# PWR_Supply.net
KiCad netlist of a schematic drawn in Altium Designer
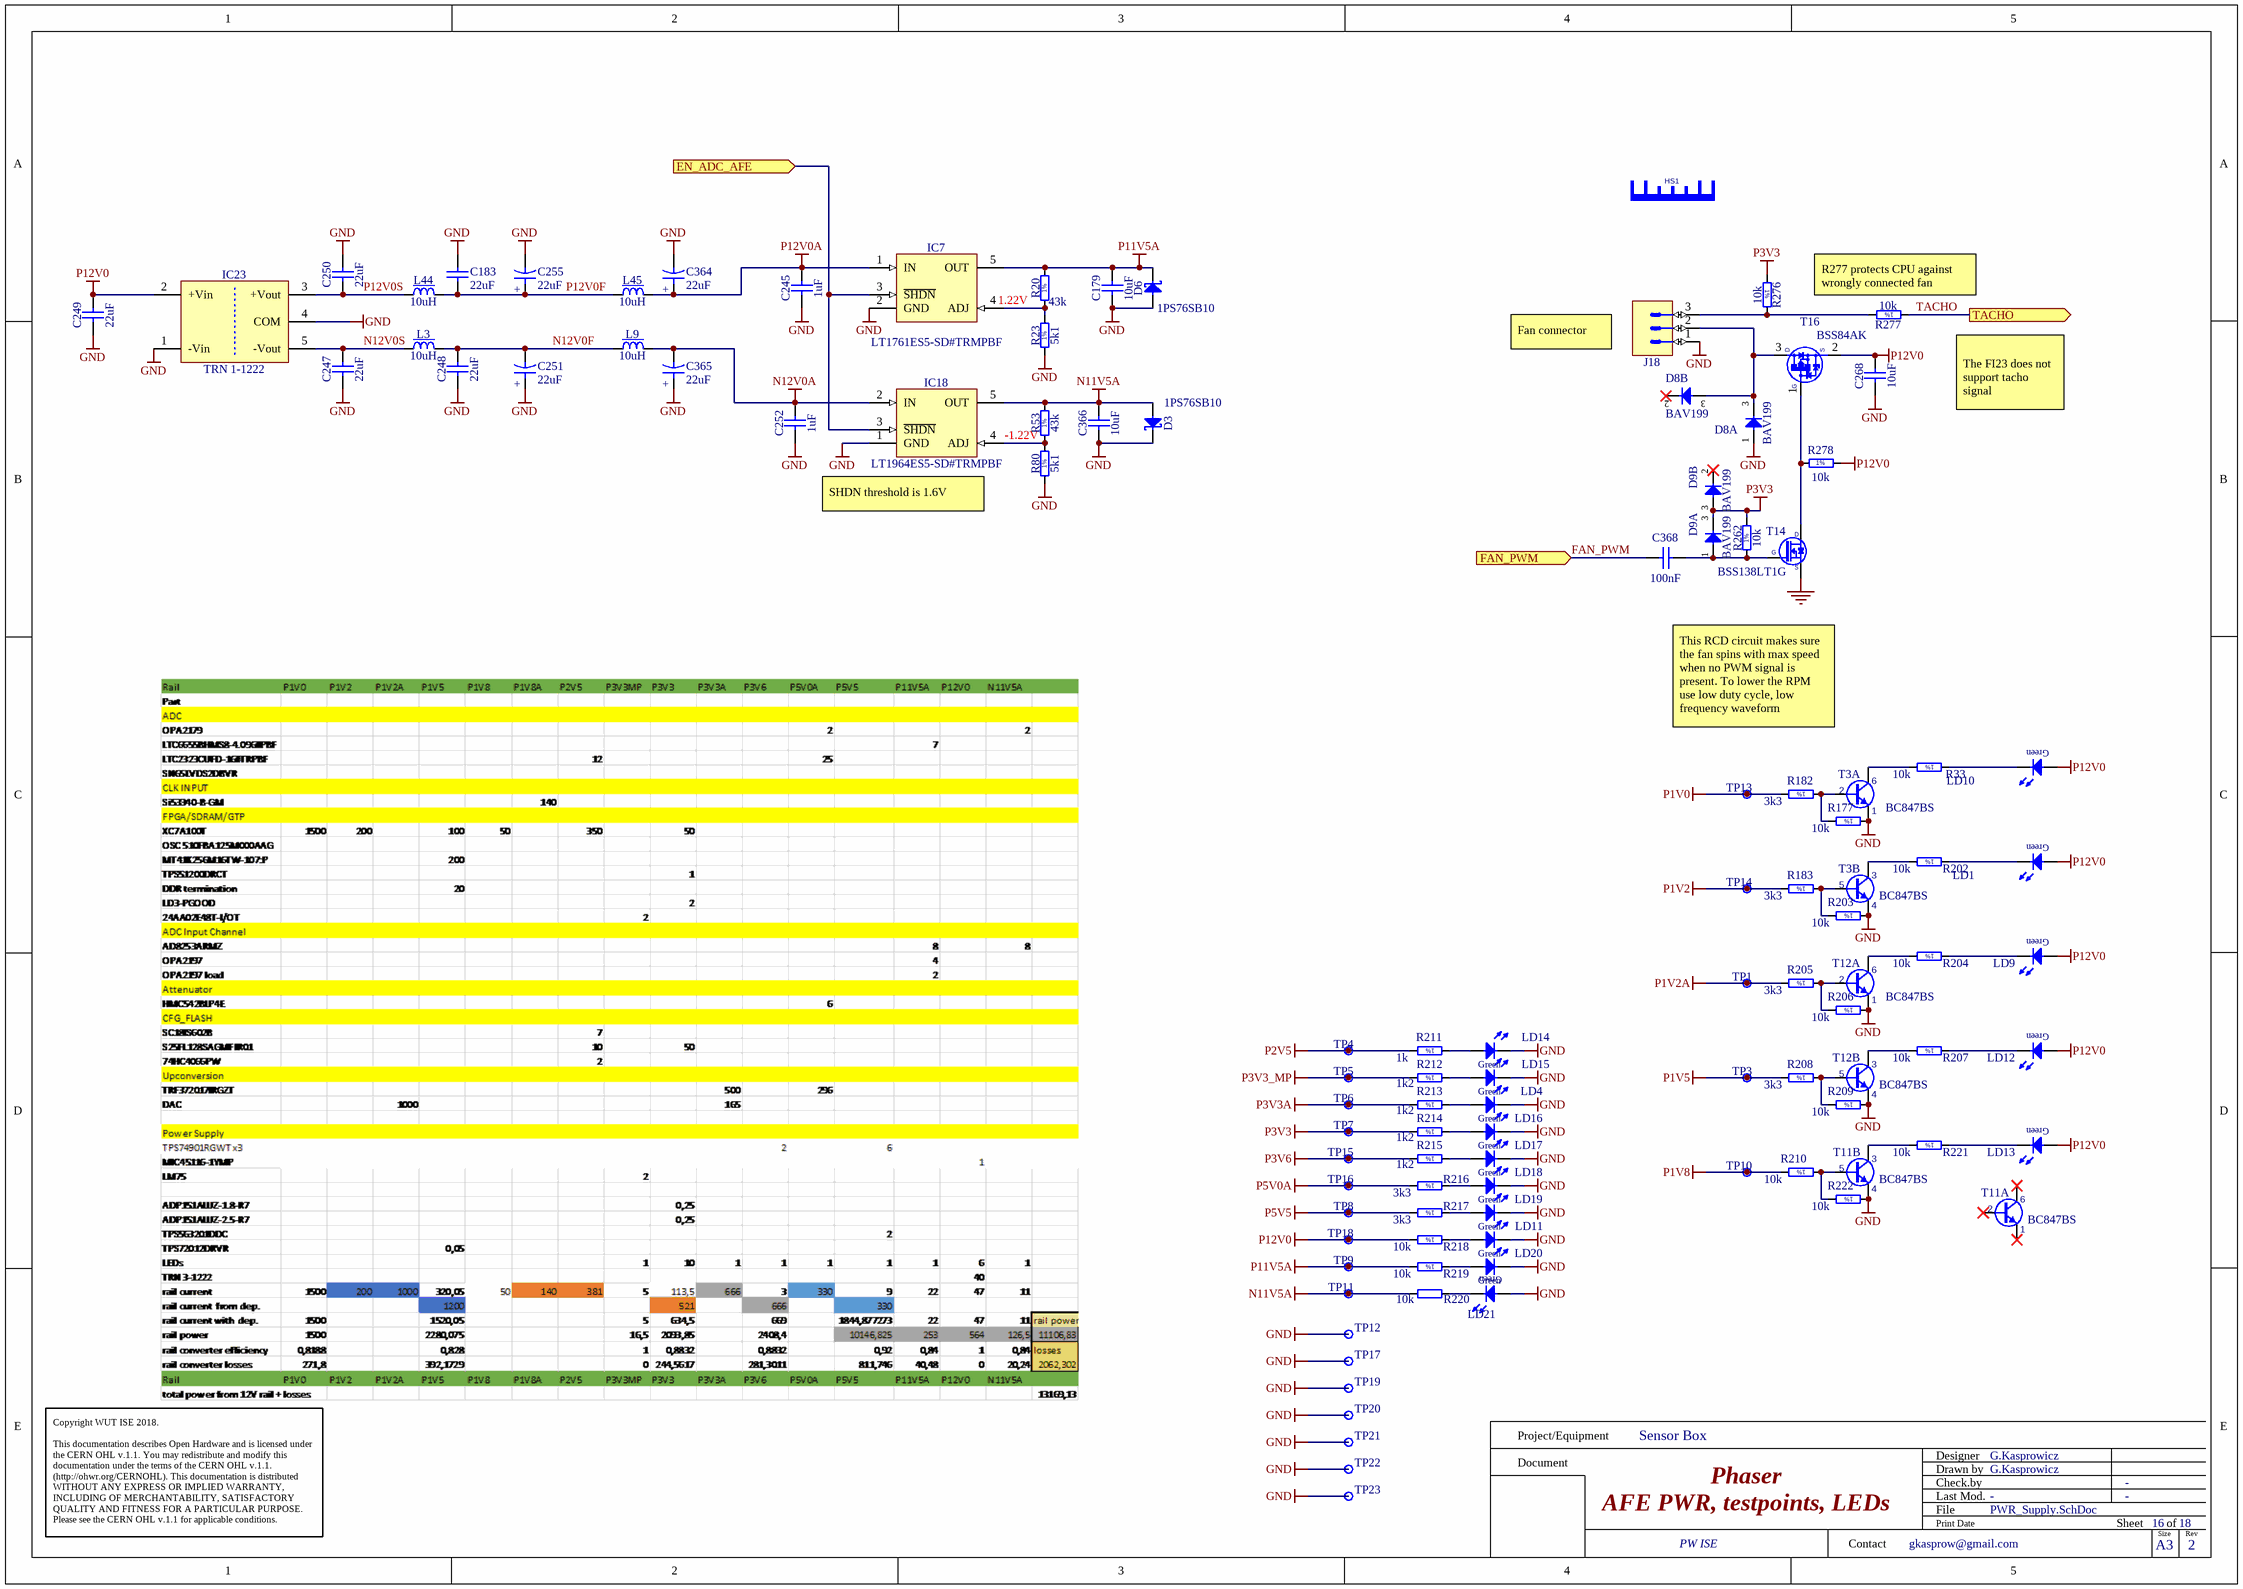
[diagram p0: PWR_Supply.SchDoc]

(export (version "E")
  (design (tool "Eeschema 10.0.6"))
  (components
    (comp (ref "C179")
      (value "10uF")
      (footprint "CAPC2012X135N")
      (description "Non-polarised capacitor")
      (fields
        (field (name "PART NUMBER") "CC0805_10UF_16V_10%_X5R")
        (field (name "VOLTAGE") "16V")
        (field (name "AUTHOR") "CERN DEM JLC")
      )
      (libsource (lib "Capacitors") (part "Capacitor - non polarized"))
    )
    (comp (ref "C183")
      (value "22uF")
      (footprint "CAPC2012X135N")
      (description "Non-polarised capacitor")
      (fields
        (field (name "PART NUMBER") "CC0805_22UF_16V_10%_X5R")
        (field (name "VOLTAGE") "16V")
        (field (name "AUTHOR") "CERN DEM JLC")
      )
      (libsource (lib "Capacitors") (part "Capacitor - non polarized"))
    )
    (comp (ref "C245")
      (value "1uF")
      (footprint "CAPC1608X87N")
      (description "Non-polarised capacitor")
      (fields
        (field (name "PART NUMBER") "CC0603_1UF_25V_10%_X7R")
        (field (name "VOLTAGE") "25V")
        (field (name "AUTHOR") "CERN DEM JLC")
      )
      (libsource (lib "Capacitors") (part "Capacitor - non polarized"))
    )
    (comp (ref "C247")
      (value "22uF")
      (footprint "CAPC2012X135N")
      (description "Non-polarised capacitor")
      (fields
        (field (name "PART NUMBER") "CC0805_22UF_16V_10%_X5R")
        (field (name "VOLTAGE") "16V")
        (field (name "AUTHOR") "CERN DEM JLC")
      )
      (libsource (lib "Capacitors") (part "Capacitor - non polarized"))
    )
    (comp (ref "C248")
      (value "22uF")
      (footprint "CAPC2012X135N")
      (description "Non-polarised capacitor")
      (fields
        (field (name "PART NUMBER") "CC0805_22UF_16V_10%_X5R")
        (field (name "VOLTAGE") "16V")
        (field (name "AUTHOR") "CERN DEM JLC")
      )
      (libsource (lib "Capacitors") (part "Capacitor - non polarized"))
    )
    (comp (ref "C249")
      (value "22uF")
      (footprint "CAPC2012X135N")
      (description "Non-polarised capacitor")
      (fields
        (field (name "PART NUMBER") "CC0805_22UF_16V_10%_X5R")
        (field (name "VOLTAGE") "16V")
        (field (name "AUTHOR") "CERN DEM JLC")
      )
      (libsource (lib "Capacitors") (part "Capacitor - non polarized"))
    )
    (comp (ref "C250")
      (value "22uF")
      (footprint "CAPC2012X135N")
      (description "Non-polarised capacitor")
      (fields
        (field (name "PART NUMBER") "CC0805_22UF_16V_10%_X5R")
        (field (name "VOLTAGE") "16V")
        (field (name "AUTHOR") "CERN DEM JLC")
      )
      (libsource (lib "Capacitors") (part "Capacitor - non polarized"))
    )
    (comp (ref "C251")
      (value "22uF")
      (footprint "CAPMP3528X210N")
      (description "Polarised capacitor")
      (fields
        (field (name "PART NUMBER") "CTE3528-21_22UF_10V_10%_LESR0700")
        (field (name "VOLTAGE") "10V")
        (field (name "AUTHOR") "CERN DEM JLC")
      )
      (libsource (lib "Capacitors") (part "Capacitor - polarized"))
    )
    (comp (ref "C252")
      (value "1uF")
      (footprint "CAPC1608X87N")
      (description "Non-polarised capacitor")
      (fields
        (field (name "PART NUMBER") "CC0603_1UF_25V_10%_X7R")
        (field (name "VOLTAGE") "25V")
        (field (name "AUTHOR") "CERN DEM JLC")
      )
      (libsource (lib "Capacitors") (part "Capacitor - non polarized"))
    )
    (comp (ref "C255")
      (value "22uF")
      (footprint "CAPMP3528X210N")
      (description "Polarised capacitor")
      (fields
        (field (name "PART NUMBER") "CTE3528-21_22UF_10V_10%_LESR0700")
        (field (name "VOLTAGE") "10V")
        (field (name "AUTHOR") "CERN DEM JLC")
      )
      (libsource (lib "Capacitors") (part "Capacitor - polarized"))
    )
    (comp (ref "C268")
      (value "10uF")
      (footprint "CAPC2012X135N")
      (description "Non-polarised capacitor")
      (fields
        (field (name "PART NUMBER") "CC0805_10UF_16V_10%_X5R")
        (field (name "VOLTAGE") "16V")
        (field (name "AUTHOR") "CERN DEM JLC")
      )
      (libsource (lib "Capacitors") (part "Capacitor - non polarized"))
    )
    (comp (ref "C364")
      (value "22uF")
      (footprint "CAPMP3528X210N")
      (description "Polarised capacitor")
      (fields
        (field (name "PART NUMBER") "CTE3528-21_22UF_10V_10%_LESR0700")
        (field (name "VOLTAGE") "10V")
        (field (name "AUTHOR") "CERN DEM JLC")
      )
      (libsource (lib "Capacitors") (part "Capacitor - polarized"))
    )
    (comp (ref "C365")
      (value "22uF")
      (footprint "CAPMP3528X210N")
      (description "Polarised capacitor")
      (fields
        (field (name "PART NUMBER") "CTE3528-21_22UF_10V_10%_LESR0700")
        (field (name "VOLTAGE") "10V")
        (field (name "AUTHOR") "CERN DEM JLC")
      )
      (libsource (lib "Capacitors") (part "Capacitor - polarized"))
    )
    (comp (ref "C366")
      (value "10uF")
      (footprint "CAPC2012X135N")
      (description "Non-polarised capacitor")
      (fields
        (field (name "PART NUMBER") "CC0805_10UF_16V_10%_X5R")
        (field (name "VOLTAGE") "16V")
        (field (name "AUTHOR") "CERN DEM JLC")
      )
      (libsource (lib "Capacitors") (part "Capacitor - non polarized"))
    )
    (comp (ref "C368")
      (value "100nF")
      (footprint "CAPC0603X33N")
      (description "Non-polarised capacitor")
      (fields
        (field (name "PART NUMBER") "CC0201_100NF_6.3V_10%_X5R")
        (field (name "VOLTAGE") "6.3V")
        (field (name "AUTHOR") "CERN DEM JLC")
      )
      (libsource (lib "Capacitors") (part "Capacitor - non polarized"))
    )
    (comp (ref "D3")
      (value "1PS76SB10")
      (footprint "SOD2512X110N")
      (description "Schottky Diode")
      (fields
        (field (name "VOLTAGE") "30V")
        (field (name "POWER") "200mA")
        (field (name "AUTHOR") "CERN DEM JLC")
      )
      (libsource (lib "ICs And Semiconductors") (part "Diode Schottky"))
    )
    (comp (ref "D6")
      (value "1PS76SB10")
      (footprint "SOD2512X110N")
      (description "Schottky Diode")
      (fields
        (field (name "VOLTAGE") "30V")
        (field (name "POWER") "200mA")
        (field (name "AUTHOR") "CERN DEM JLC")
      )
      (libsource (lib "ICs And Semiconductors") (part "Diode Schottky"))
    )
    (comp (ref "D8")
      (value "BAV199")
      (footprint "SOT95P240X110-3N")
      (description "Serial Diode")
      (fields
        (field (name "VOLTAGE") "75V")
        (field (name "POWER") "250mW")
        (field (name "AUTHOR") "CERN DEM JMW")
      )
      (libsource (lib "ICs And Semiconductors") (part "Diode x2 A1C3_A3C2"))
    )
    (comp (ref "D9")
      (value "BAV199")
      (footprint "SOT95P240X110-3N")
      (description "Serial Diode")
      (fields
        (field (name "VOLTAGE") "75V")
        (field (name "POWER") "250mW")
        (field (name "AUTHOR") "CERN DEM JMW")
      )
      (libsource (lib "ICs And Semiconductors") (part "Diode x2 A1C3_A3C2"))
    )
    (comp (ref "HS1")
      (value "RADIAN_FI23")
      (footprint "RADIAN_FI23")
      (description "Heat Sink Without Pad")
      (fields
        (field (name "MANUFACTURER") "Radian Thermal Products, Inc.")
        (field (name "MANUFACTURER PART NUMBER") "FI23+BU+T725")
      )
      (libsource (lib "Schlib1") (part "RADIAN_FI23"))
    )
    (comp (ref "IC7")
      (value "LT1761ES5-SD#TRMPBF")
      (footprint "SOT95P280X100-5N")
      (description "100mA, Low Noise, LDO Micropower Adjustable Regulator in SOT-23")
      (fields (field (name "MANUFACTURER") "LINEAR TECHNOLOGY") (field (name "AUTHOR") "CERN DEM JLC"))
      (libsource (lib "ICs And Semiconductors") (part "LT1761-SD"))
    )
    (comp (ref "IC18")
      (value "LT1964ES5-SD#TRMPBF")
      (footprint "SOT95P280X100-5N")
      (description "200mA, Low Noise, Low Dropout Negative Micropower Regulator")
      (fields (field (name "MANUFACTURER") "LINEAR TECHNOLOGY") (field (name "AUTHOR") "CERN DEM JLC"))
      (libsource (lib "ICs And Semiconductors") (part "LT1964-SD"))
    )
    (comp (ref "IC23")
      (value "TRN 1-1222")
      (footprint "DCDC_TRACO_TRN1")
      (description "9-18VDC to ±12V, Iout (max) ±45mA, 1W DC-DC Converter")
      (fields (field (name "MANUFACTURER") "TRACO POWER") (field (name "AUTHOR") "GK"))
      (libsource (lib "Regulators_SMPS") (part "DCDC_TRACO_TRN 1-1222"))
    )
    (comp (ref "J18")
      (value "KK®")
      (footprint "MOLEX_22-27-2031")
      (description "Connector 3 Male")
      (fields
        (field (name "PART NUMBER") "MOLEX_22-27-2031")
        (field (name "MANUFACTURER") "MOLEX")
        (field (name "AUTHOR") "CERN DEM JLC")
      )
      (libsource (lib "Connectors") (part "Connector 3 Male"))
    )
    (comp (ref "L3")
      (value "10uH")
      (footprint "IND_MURATA-PS_8400")
      (description "Inductor With Core")
      (fields
        (field (name "PART NUMBER") "IND_10UH_10%_MURATA-PS_8400")
        (field (name "POWER") "950mA")
        (field (name "AUTHOR") "CERN DEM JLC")
      )
      (libsource (lib "Inductors & Transformers") (part "Inductor With Magnetic core"))
    )
    (comp (ref "L9")
      (value "10uH")
      (footprint "IND_MURATA-PS_8400")
      (description "Inductor With Core")
      (fields
        (field (name "PART NUMBER") "IND_10UH_10%_MURATA-PS_8400")
        (field (name "POWER") "950mA")
        (field (name "AUTHOR") "CERN DEM JLC")
      )
      (libsource (lib "Inductors & Transformers") (part "Inductor With Magnetic core"))
    )
    (comp (ref "L44")
      (value "10uH")
      (footprint "IND_MURATA-PS_8400")
      (description "Inductor With Core")
      (fields
        (field (name "PART NUMBER") "IND_10UH_10%_MURATA-PS_8400")
        (field (name "POWER") "950mA")
        (field (name "AUTHOR") "CERN DEM JLC")
      )
      (libsource (lib "Inductors & Transformers") (part "Inductor With Magnetic core"))
    )
    (comp (ref "L45")
      (value "10uH")
      (footprint "IND_MURATA-PS_8400")
      (description "Inductor With Core")
      (fields
        (field (name "PART NUMBER") "IND_10UH_10%_MURATA-PS_8400")
        (field (name "POWER") "950mA")
        (field (name "AUTHOR") "CERN DEM JLC")
      )
      (libsource (lib "Inductors & Transformers") (part "Inductor With Magnetic core"))
    )
    (comp (ref "LD1")
      (value "Green")
      (footprint "LED_KINGBRIGHT_KPH-1608CGCKr")
      (description "Green 0603")
      (fields
        (field (name "PART NUMBER") "LED_KINGBRIGHT_KPH-1608CGCK")
        (field (name "MANUFACTURER") "KINGBRIGHT")
        (field (name "AUTHOR") "CERN DEM JLC")
      )
      (libsource (lib "LIBRARY_SCH") (part "LED_0603_Green"))
    )
    (comp (ref "LD4")
      (value "Green")
      (footprint "LED_KINGBRIGHT_KPH-1608CGCKr")
      (description "Green 0603")
      (fields
        (field (name "PART NUMBER") "LED_KINGBRIGHT_KPH-1608CGCK")
        (field (name "MANUFACTURER") "KINGBRIGHT")
        (field (name "AUTHOR") "CERN DEM JLC")
      )
      (libsource (lib "LIBRARY_SCH") (part "LED_0603_Green"))
    )
    (comp (ref "LD9")
      (value "Green")
      (footprint "LED_KINGBRIGHT_KPH-1608CGCKr")
      (description "Green 0603")
      (fields
        (field (name "PART NUMBER") "LED_KINGBRIGHT_KPH-1608CGCK")
        (field (name "MANUFACTURER") "KINGBRIGHT")
        (field (name "AUTHOR") "CERN DEM JLC")
      )
      (libsource (lib "LIBRARY_SCH") (part "LED_0603_Green"))
    )
    (comp (ref "LD10")
      (value "Green")
      (footprint "LED_KINGBRIGHT_KPH-1608CGCKr")
      (description "Green 0603")
      (fields
        (field (name "PART NUMBER") "LED_KINGBRIGHT_KPH-1608CGCK")
        (field (name "MANUFACTURER") "KINGBRIGHT")
        (field (name "AUTHOR") "CERN DEM JLC")
      )
      (libsource (lib "LIBRARY_SCH") (part "LED_0603_Green"))
    )
    (comp (ref "LD11")
      (value "Green")
      (footprint "LED_KINGBRIGHT_KPH-1608CGCKr")
      (description "Green 0603")
      (fields
        (field (name "PART NUMBER") "LED_KINGBRIGHT_KPH-1608CGCK")
        (field (name "MANUFACTURER") "KINGBRIGHT")
        (field (name "AUTHOR") "CERN DEM JLC")
      )
      (libsource (lib "LIBRARY_SCH") (part "LED_0603_Green"))
    )
    (comp (ref "LD12")
      (value "Green")
      (footprint "LED_KINGBRIGHT_KPH-1608CGCKr")
      (description "Green 0603")
      (fields
        (field (name "PART NUMBER") "LED_KINGBRIGHT_KPH-1608CGCK")
        (field (name "MANUFACTURER") "KINGBRIGHT")
        (field (name "AUTHOR") "CERN DEM JLC")
      )
      (libsource (lib "LIBRARY_SCH") (part "LED_0603_Green"))
    )
    (comp (ref "LD13")
      (value "Green")
      (footprint "LED_KINGBRIGHT_KPH-1608CGCKr")
      (description "Green 0603")
      (fields
        (field (name "PART NUMBER") "LED_KINGBRIGHT_KPH-1608CGCK")
        (field (name "MANUFACTURER") "KINGBRIGHT")
        (field (name "AUTHOR") "CERN DEM JLC")
      )
      (libsource (lib "LIBRARY_SCH") (part "LED_0603_Green"))
    )
    (comp (ref "LD14")
      (value "Green")
      (footprint "LED_KINGBRIGHT_KPH-1608CGCKr")
      (description "Green 0603")
      (fields
        (field (name "PART NUMBER") "LED_KINGBRIGHT_KPH-1608CGCK")
        (field (name "MANUFACTURER") "KINGBRIGHT")
        (field (name "AUTHOR") "CERN DEM JLC")
      )
      (libsource (lib "LIBRARY_SCH") (part "LED_0603_Green"))
    )
    (comp (ref "LD15")
      (value "Green")
      (footprint "LED_KINGBRIGHT_KPH-1608CGCKr")
      (description "Green 0603")
      (fields
        (field (name "PART NUMBER") "LED_KINGBRIGHT_KPH-1608CGCK")
        (field (name "MANUFACTURER") "KINGBRIGHT")
        (field (name "AUTHOR") "CERN DEM JLC")
      )
      (libsource (lib "LIBRARY_SCH") (part "LED_0603_Green"))
    )
    (comp (ref "LD16")
      (value "Green")
      (footprint "LED_KINGBRIGHT_KPH-1608CGCKr")
      (description "Green 0603")
      (fields
        (field (name "PART NUMBER") "LED_KINGBRIGHT_KPH-1608CGCK")
        (field (name "MANUFACTURER") "KINGBRIGHT")
        (field (name "AUTHOR") "CERN DEM JLC")
      )
      (libsource (lib "LIBRARY_SCH") (part "LED_0603_Green"))
    )
    (comp (ref "LD17")
      (value "Green")
      (footprint "LED_KINGBRIGHT_KPH-1608CGCKr")
      (description "Green 0603")
      (fields
        (field (name "PART NUMBER") "LED_KINGBRIGHT_KPH-1608CGCK")
        (field (name "MANUFACTURER") "KINGBRIGHT")
        (field (name "AUTHOR") "CERN DEM JLC")
      )
      (libsource (lib "LIBRARY_SCH") (part "LED_0603_Green"))
    )
    (comp (ref "LD18")
      (value "Green")
      (footprint "LED_KINGBRIGHT_KPH-1608CGCKr")
      (description "Green 0603")
      (fields
        (field (name "PART NUMBER") "LED_KINGBRIGHT_KPH-1608CGCK")
        (field (name "MANUFACTURER") "KINGBRIGHT")
        (field (name "AUTHOR") "CERN DEM JLC")
      )
      (libsource (lib "LIBRARY_SCH") (part "LED_0603_Green"))
    )
    (comp (ref "LD19")
      (value "Green")
      (footprint "LED_KINGBRIGHT_KPH-1608CGCKr")
      (description "Green 0603")
      (fields
        (field (name "PART NUMBER") "LED_KINGBRIGHT_KPH-1608CGCK")
        (field (name "MANUFACTURER") "KINGBRIGHT")
        (field (name "AUTHOR") "CERN DEM JLC")
      )
      (libsource (lib "LIBRARY_SCH") (part "LED_0603_Green"))
    )
    (comp (ref "LD20")
      (value "Green")
      (footprint "LED_KINGBRIGHT_KPH-1608CGCKr")
      (description "Green 0603")
      (fields
        (field (name "PART NUMBER") "LED_KINGBRIGHT_KPH-1608CGCK")
        (field (name "MANUFACTURER") "KINGBRIGHT")
        (field (name "AUTHOR") "CERN DEM JLC")
      )
      (libsource (lib "LIBRARY_SCH") (part "LED_0603_Green"))
    )
    (comp (ref "LD21")
      (value "Green")
      (footprint "LED_KINGBRIGHT_KPH-1608CGCKr")
      (description "Green 0603")
      (fields
        (field (name "PART NUMBER") "LED_KINGBRIGHT_KPH-1608CGCK")
        (field (name "MANUFACTURER") "KINGBRIGHT")
        (field (name "AUTHOR") "CERN DEM JLC")
      )
      (libsource (lib "LIBRARY_SCH") (part "LED_0603_Green"))
    )
    (comp (ref "R20")
      (value "43k")
      (footprint "RESC1005X40N")
      (description "Resistor - 1%")
      (fields
        (field (name "PART NUMBER") "R0402_43K_1%_0.0625W_100PPM")
        (field (name "POWER") "0.0625W")
        (field (name "AUTHOR") "CERN DEM JLC")
      )
      (libsource (lib "Resistors") (part "Resistor - 1%"))
    )
    (comp (ref "R23")
      (value "5k1")
      (footprint "RESC1005X40N")
      (description "Resistor - 1%")
      (fields
        (field (name "PART NUMBER") "R0402_5K1_1%_0.0625W_100PPM")
        (field (name "POWER") "0.0625W")
        (field (name "AUTHOR") "CERN DEM JLC")
      )
      (libsource (lib "Resistors") (part "Resistor - 1%"))
    )
    (comp (ref "R33")
      (value "10k")
      (footprint "RESC1005X40N")
      (description "Resistor - 1%")
      (fields
        (field (name "PART NUMBER") "R0402_10K_1%_0.0625W_100PPM")
        (field (name "POWER") "0.0625W")
        (field (name "AUTHOR") "CERN DEM JLC")
      )
      (libsource (lib "Resistors") (part "Resistor - 1%"))
    )
    (comp (ref "R53")
      (value "43k")
      (footprint "RESC1005X40N")
      (description "Resistor - 1%")
      (fields
        (field (name "PART NUMBER") "R0402_43K_1%_0.0625W_100PPM")
        (field (name "POWER") "0.0625W")
        (field (name "AUTHOR") "CERN DEM JLC")
      )
      (libsource (lib "Resistors") (part "Resistor - 1%"))
    )
    (comp (ref "R80")
      (value "5k1")
      (footprint "RESC1005X40N")
      (description "Resistor - 1%")
      (fields
        (field (name "PART NUMBER") "R0402_5K1_1%_0.0625W_100PPM")
        (field (name "POWER") "0.0625W")
        (field (name "AUTHOR") "CERN DEM JLC")
      )
      (libsource (lib "Resistors") (part "Resistor - 1%"))
    )
    (comp (ref "R177")
      (value "10k")
      (footprint "RESC1005X40N")
      (description "Resistor - 1%")
      (fields
        (field (name "PART NUMBER") "R0402_10K_1%_0.0625W_100PPM")
        (field (name "POWER") "0.0625W")
        (field (name "AUTHOR") "CERN DEM JLC")
      )
      (libsource (lib "Resistors") (part "Resistor - 1%"))
    )
    (comp (ref "R182")
      (value "3k3")
      (footprint "RESC1608X55N")
      (description "Resistor - 1%")
      (fields
        (field (name "PART NUMBER") "R0603_3K3_1%_0.1W_100PPM")
        (field (name "POWER") "0.1W")
        (field (name "AUTHOR") "CERN DEM JLC")
      )
      (libsource (lib "Resistors") (part "Resistor - 1%"))
    )
    (comp (ref "R183")
      (value "3k3")
      (footprint "RESC1608X55N")
      (description "Resistor - 1%")
      (fields
        (field (name "PART NUMBER") "R0603_3K3_1%_0.1W_100PPM")
        (field (name "POWER") "0.1W")
        (field (name "AUTHOR") "CERN DEM JLC")
      )
      (libsource (lib "Resistors") (part "Resistor - 1%"))
    )
    (comp (ref "R202")
      (value "10k")
      (footprint "RESC1005X40N")
      (description "Resistor - 1%")
      (fields
        (field (name "PART NUMBER") "R0402_10K_1%_0.0625W_100PPM")
        (field (name "POWER") "0.0625W")
        (field (name "AUTHOR") "CERN DEM JLC")
      )
      (libsource (lib "Resistors") (part "Resistor - 1%"))
    )
    (comp (ref "R203")
      (value "10k")
      (footprint "RESC1005X40N")
      (description "Resistor - 1%")
      (fields
        (field (name "PART NUMBER") "R0402_10K_1%_0.0625W_100PPM")
        (field (name "POWER") "0.0625W")
        (field (name "AUTHOR") "CERN DEM JLC")
      )
      (libsource (lib "Resistors") (part "Resistor - 1%"))
    )
    (comp (ref "R204")
      (value "10k")
      (footprint "RESC1005X40N")
      (description "Resistor - 1%")
      (fields
        (field (name "PART NUMBER") "R0402_10K_1%_0.0625W_100PPM")
        (field (name "POWER") "0.0625W")
        (field (name "AUTHOR") "CERN DEM JLC")
      )
      (libsource (lib "Resistors") (part "Resistor - 1%"))
    )
    (comp (ref "R205")
      (value "3k3")
      (footprint "RESC1608X55N")
      (description "Resistor - 1%")
      (fields
        (field (name "PART NUMBER") "R0603_3K3_1%_0.1W_100PPM")
        (field (name "POWER") "0.1W")
        (field (name "AUTHOR") "CERN DEM JLC")
      )
      (libsource (lib "Resistors") (part "Resistor - 1%"))
    )
    (comp (ref "R206")
      (value "10k")
      (footprint "RESC1005X40N")
      (description "Resistor - 1%")
      (fields
        (field (name "PART NUMBER") "R0402_10K_1%_0.0625W_100PPM")
        (field (name "POWER") "0.0625W")
        (field (name "AUTHOR") "CERN DEM JLC")
      )
      (libsource (lib "Resistors") (part "Resistor - 1%"))
    )
    (comp (ref "R207")
      (value "10k")
      (footprint "RESC1005X40N")
      (description "Resistor - 1%")
      (fields
        (field (name "PART NUMBER") "R0402_10K_1%_0.0625W_100PPM")
        (field (name "POWER") "0.0625W")
        (field (name "AUTHOR") "CERN DEM JLC")
      )
      (libsource (lib "Resistors") (part "Resistor - 1%"))
    )
    (comp (ref "R208")
      (value "3k3")
      (footprint "RESC1608X55N")
      (description "Resistor - 1%")
      (fields
        (field (name "PART NUMBER") "R0603_3K3_1%_0.1W_100PPM")
        (field (name "POWER") "0.1W")
        (field (name "AUTHOR") "CERN DEM JLC")
      )
      (libsource (lib "Resistors") (part "Resistor - 1%"))
    )
    (comp (ref "R209")
      (value "10k")
      (footprint "RESC1005X40N")
      (description "Resistor - 1%")
      (fields
        (field (name "PART NUMBER") "R0402_10K_1%_0.0625W_100PPM")
        (field (name "POWER") "0.0625W")
        (field (name "AUTHOR") "CERN DEM JLC")
      )
      (libsource (lib "Resistors") (part "Resistor - 1%"))
    )
    (comp (ref "R210")
      (value "10k")
      (footprint "RESC1005X40N")
      (description "Resistor - 1%")
      (fields
        (field (name "PART NUMBER") "R0402_10K_1%_0.0625W_100PPM")
        (field (name "POWER") "0.0625W")
        (field (name "AUTHOR") "CERN DEM JLC")
      )
      (libsource (lib "Resistors") (part "Resistor - 1%"))
    )
    (comp (ref "R211")
      (value "1k")
      (footprint "RESC1608X55N")
      (description "Resistor - 1%")
      (fields
        (field (name "PART NUMBER") "R0603_1K_1%_0.1W_100PPM")
        (field (name "POWER") "0.1W")
        (field (name "AUTHOR") "CERN DEM JLC")
      )
      (libsource (lib "Resistors") (part "Resistor - 1%"))
    )
    (comp (ref "R212")
      (value "1k2")
      (footprint "RESC1608X55N")
      (description "Resistor - 1%")
      (fields
        (field (name "PART NUMBER") "R0603_1K2_1%_0.1W_100PPM")
        (field (name "POWER") "0.1W")
        (field (name "AUTHOR") "CERN DEM JLC")
      )
      (libsource (lib "Resistors") (part "Resistor - 1%"))
    )
    (comp (ref "R213")
      (value "1k2")
      (footprint "RESC1608X55N")
      (description "Resistor - 1%")
      (fields
        (field (name "PART NUMBER") "R0603_1K2_1%_0.1W_100PPM")
        (field (name "POWER") "0.1W")
        (field (name "AUTHOR") "CERN DEM JLC")
      )
      (libsource (lib "Resistors") (part "Resistor - 1%"))
    )
    (comp (ref "R214")
      (value "1k2")
      (footprint "RESC1608X55N")
      (description "Resistor - 1%")
      (fields
        (field (name "PART NUMBER") "R0603_1K2_1%_0.1W_100PPM")
        (field (name "POWER") "0.1W")
        (field (name "AUTHOR") "CERN DEM JLC")
      )
      (libsource (lib "Resistors") (part "Resistor - 1%"))
    )
    (comp (ref "R215")
      (value "1k2")
      (footprint "RESC1608X55N")
      (description "Resistor - 1%")
      (fields
        (field (name "PART NUMBER") "R0603_1K2_1%_0.1W_100PPM")
        (field (name "POWER") "0.1W")
        (field (name "AUTHOR") "CERN DEM JLC")
      )
      (libsource (lib "Resistors") (part "Resistor - 1%"))
    )
    (comp (ref "R216")
      (value "3k3")
      (footprint "RESC1608X55N")
      (description "Resistor - 1%")
      (fields
        (field (name "PART NUMBER") "R0603_3K3_1%_0.1W_100PPM")
        (field (name "POWER") "0.1W")
        (field (name "AUTHOR") "CERN DEM JLC")
      )
      (libsource (lib "Resistors") (part "Resistor - 1%"))
    )
    (comp (ref "R217")
      (value "3k3")
      (footprint "RESC1608X55N")
      (description "Resistor - 1%")
      (fields
        (field (name "PART NUMBER") "R0603_3K3_1%_0.1W_100PPM")
        (field (name "POWER") "0.1W")
        (field (name "AUTHOR") "CERN DEM JLC")
      )
      (libsource (lib "Resistors") (part "Resistor - 1%"))
    )
    (comp (ref "R218")
      (value "10k")
      (footprint "RESC1005X40N")
      (description "Resistor - 1%")
      (fields
        (field (name "PART NUMBER") "R0402_10K_1%_0.0625W_100PPM")
        (field (name "POWER") "0.0625W")
        (field (name "AUTHOR") "CERN DEM JLC")
      )
      (libsource (lib "Resistors") (part "Resistor - 1%"))
    )
    (comp (ref "R219")
      (value "10k")
      (footprint "RESC1005X40N")
      (description "Resistor - 1%")
      (fields
        (field (name "PART NUMBER") "R0402_10K_1%_0.0625W_100PPM")
        (field (name "POWER") "0.0625W")
        (field (name "AUTHOR") "CERN DEM JLC")
      )
      (libsource (lib "Resistors") (part "Resistor - 1%"))
    )
    (comp (ref "R220")
      (value "10k")
      (footprint "RESC1608X55N")
      (description "Resistor - 1%")
      (fields
        (field (name "PART NUMBER") "R0603_10K_1%_0.1W_100PPM")
        (field (name "POWER") "0.1W")
        (field (name "AUTHOR") "CERN DEM JLC")
      )
      (libsource (lib "") (part "Resistor - 1%_1"))
    )
    (comp (ref "R221")
      (value "10k")
      (footprint "RESC1005X40N")
      (description "Resistor - 1%")
      (fields
        (field (name "PART NUMBER") "R0402_10K_1%_0.0625W_100PPM")
        (field (name "POWER") "0.0625W")
        (field (name "AUTHOR") "CERN DEM JLC")
      )
      (libsource (lib "Resistors") (part "Resistor - 1%"))
    )
    (comp (ref "R222")
      (value "10k")
      (footprint "RESC1005X40N")
      (description "Resistor - 1%")
      (fields
        (field (name "PART NUMBER") "R0402_10K_1%_0.0625W_100PPM")
        (field (name "POWER") "0.0625W")
        (field (name "AUTHOR") "CERN DEM JLC")
      )
      (libsource (lib "Resistors") (part "Resistor - 1%"))
    )
    (comp (ref "R262")
      (value "10k")
      (footprint "RESC1005X40N")
      (description "Resistor - 1%")
      (fields
        (field (name "PART NUMBER") "R0402_10K_1%_0.0625W_100PPM")
        (field (name "POWER") "0.0625W")
        (field (name "AUTHOR") "CERN DEM JLC")
      )
      (libsource (lib "Resistors") (part "Resistor - 1%"))
    )
    (comp (ref "R276")
      (value "10k")
      (footprint "RESC1005X40N")
      (description "Resistor - 1%")
      (fields
        (field (name "PART NUMBER") "R0402_10K_1%_0.0625W_100PPM")
        (field (name "POWER") "0.0625W")
        (field (name "AUTHOR") "CERN DEM JLC")
      )
      (libsource (lib "Resistors") (part "Resistor - 1%"))
    )
    (comp (ref "R277")
      (value "10k")
      (footprint "RESC1005X40N")
      (description "Resistor - 1%")
      (fields
        (field (name "PART NUMBER") "R0402_10K_1%_0.0625W_100PPM")
        (field (name "POWER") "0.0625W")
        (field (name "AUTHOR") "CERN DEM JLC")
      )
      (libsource (lib "Resistors") (part "Resistor - 1%"))
    )
    (comp (ref "R278")
      (value "10k")
      (footprint "RESC1005X40N")
      (description "Resistor - 1%")
      (fields
        (field (name "PART NUMBER") "R0402_10K_1%_0.0625W_100PPM")
        (field (name "POWER") "0.0625W")
        (field (name "AUTHOR") "CERN DEM JLC")
      )
      (libsource (lib "Resistors") (part "Resistor - 1%"))
    )
    (comp (ref "T3")
      (value "BC847BS")
      (footprint "SOT65P210X110-6N")
      (description "45V 100mA Dual NPN General-Purpose Transistor")
      (fields (field (name "MANUFACTURER") "NXP SEMICONDUCTORS") (field (name "AUTHOR") "CERN DEM JMW"))
      (libsource (lib "ICs And Semiconductors") (part "BC847BS"))
    )
    (comp (ref "T11")
      (value "BC847BS")
      (footprint "SOT65P210X110-6N")
      (description "45V 100mA Dual NPN General-Purpose Transistor")
      (fields (field (name "MANUFACTURER") "NXP SEMICONDUCTORS") (field (name "AUTHOR") "CERN DEM JMW"))
      (libsource (lib "ICs And Semiconductors") (part "BC847BS"))
    )
    (comp (ref "T12")
      (value "BC847BS")
      (footprint "SOT65P210X110-6N")
      (description "45V 100mA Dual NPN General-Purpose Transistor")
      (fields (field (name "MANUFACTURER") "NXP SEMICONDUCTORS") (field (name "AUTHOR") "CERN DEM JMW"))
      (libsource (lib "ICs And Semiconductors") (part "BC847BS"))
    )
    (comp (ref "T14")
      (value "BSS138LT1G")
      (footprint "SOT95P240X110-3N")
      (description "N-CHANNEL MOSFET WITH DIODE")
      (fields (field (name "MANUFACTURER") "ON SEMICONDUCTOR") (field (name "AUTHOR") "CERN DEM JLC"))
      (libsource (lib "ICs And Semiconductors") (part "N-MOSFET-D 1G 2S 3D"))
    )
    (comp (ref "T16")
      (value "BSS84AK")
      (footprint "SOT95P230X110-3N")
      (description "50V, 180mA P-Channel Trench MOSFET")
      (fields (field (name "MANUFACTURER") "NXP SEMICONDUCTORS") (field (name "AUTHOR") "CERN DEM JLC"))
      (libsource (lib "ICs And Semiconductors") (part "BSS84"))
    )
    (comp (ref "TP1")
      (value "Test Point")
      (footprint "TPS127")
      (fields (field (name "PART NUMBER") "SMD_PAD_1.27X1.27MM") (field (name "AUTHOR") "CERN DEM JLC"))
      (libsource (lib "Eletro-mechanical") (part "Test Point"))
    )
    (comp (ref "TP3")
      (value "Test Point")
      (footprint "TPS127")
      (fields (field (name "PART NUMBER") "SMD_PAD_1.27X1.27MM") (field (name "AUTHOR") "CERN DEM JLC"))
      (libsource (lib "Eletro-mechanical") (part "Test Point"))
    )
    (comp (ref "TP4")
      (value "Test Point")
      (footprint "TPS127")
      (fields (field (name "PART NUMBER") "SMD_PAD_1.27X1.27MM") (field (name "AUTHOR") "CERN DEM JLC"))
      (libsource (lib "Eletro-mechanical") (part "Test Point"))
    )
    (comp (ref "TP5")
      (value "Test Point")
      (footprint "TPS127")
      (fields (field (name "PART NUMBER") "SMD_PAD_1.27X1.27MM") (field (name "AUTHOR") "CERN DEM JLC"))
      (libsource (lib "Eletro-mechanical") (part "Test Point"))
    )
    (comp (ref "TP6")
      (value "Test Point")
      (footprint "TPS127")
      (fields (field (name "PART NUMBER") "SMD_PAD_1.27X1.27MM") (field (name "AUTHOR") "CERN DEM JLC"))
      (libsource (lib "Eletro-mechanical") (part "Test Point"))
    )
    (comp (ref "TP7")
      (value "Test Point")
      (footprint "TPS127")
      (fields (field (name "PART NUMBER") "SMD_PAD_1.27X1.27MM") (field (name "AUTHOR") "CERN DEM JLC"))
      (libsource (lib "Eletro-mechanical") (part "Test Point"))
    )
    (comp (ref "TP8")
      (value "Test Point")
      (footprint "TPS127")
      (fields (field (name "PART NUMBER") "SMD_PAD_1.27X1.27MM") (field (name "AUTHOR") "CERN DEM JLC"))
      (libsource (lib "Eletro-mechanical") (part "Test Point"))
    )
    (comp (ref "TP9")
      (value "Test Point")
      (footprint "TPS127")
      (fields (field (name "PART NUMBER") "SMD_PAD_1.27X1.27MM") (field (name "AUTHOR") "CERN DEM JLC"))
      (libsource (lib "Eletro-mechanical") (part "Test Point"))
    )
    (comp (ref "TP10")
      (value "Test Point")
      (footprint "TPS127")
      (fields (field (name "PART NUMBER") "SMD_PAD_1.27X1.27MM") (field (name "AUTHOR") "CERN DEM JLC"))
      (libsource (lib "Eletro-mechanical") (part "Test Point"))
    )
    (comp (ref "TP11")
      (value "Test Point")
      (footprint "TPS127")
      (fields (field (name "PART NUMBER") "SMD_PAD_1.27X1.27MM") (field (name "AUTHOR") "CERN DEM JLC"))
      (libsource (lib "Eletro-mechanical") (part "Test Point"))
    )
    (comp (ref "TP12")
      (value "Test Point")
      (footprint "TPS127")
      (fields (field (name "PART NUMBER") "SMD_PAD_1.27X1.27MM") (field (name "AUTHOR") "CERN DEM JLC"))
      (libsource (lib "Eletro-mechanical") (part "Test Point"))
    )
    (comp (ref "TP13")
      (value "Test Point")
      (footprint "TPS127")
      (fields (field (name "PART NUMBER") "SMD_PAD_1.27X1.27MM") (field (name "AUTHOR") "CERN DEM JLC"))
      (libsource (lib "Eletro-mechanical") (part "Test Point"))
    )
    (comp (ref "TP14")
      (value "Test Point")
      (footprint "TPS127")
      (fields (field (name "PART NUMBER") "SMD_PAD_1.27X1.27MM") (field (name "AUTHOR") "CERN DEM JLC"))
      (libsource (lib "Eletro-mechanical") (part "Test Point"))
    )
    (comp (ref "TP15")
      (value "Test Point")
      (footprint "TPS127")
      (fields (field (name "PART NUMBER") "SMD_PAD_1.27X1.27MM") (field (name "AUTHOR") "CERN DEM JLC"))
      (libsource (lib "Eletro-mechanical") (part "Test Point"))
    )
    (comp (ref "TP16")
      (value "Test Point")
      (footprint "TPS127")
      (fields (field (name "PART NUMBER") "SMD_PAD_1.27X1.27MM") (field (name "AUTHOR") "CERN DEM JLC"))
      (libsource (lib "Eletro-mechanical") (part "Test Point"))
    )
    (comp (ref "TP17")
      (value "Test Point")
      (footprint "TPS127")
      (fields (field (name "PART NUMBER") "SMD_PAD_1.27X1.27MM") (field (name "AUTHOR") "CERN DEM JLC"))
      (libsource (lib "Eletro-mechanical") (part "Test Point"))
    )
    (comp (ref "TP18")
      (value "Test Point")
      (footprint "TPS127")
      (fields (field (name "PART NUMBER") "SMD_PAD_1.27X1.27MM") (field (name "AUTHOR") "CERN DEM JLC"))
      (libsource (lib "Eletro-mechanical") (part "Test Point"))
    )
    (comp (ref "TP19")
      (value "Test Point")
      (footprint "TPS127")
      (fields (field (name "PART NUMBER") "SMD_PAD_1.27X1.27MM") (field (name "AUTHOR") "CERN DEM JLC"))
      (libsource (lib "Eletro-mechanical") (part "Test Point"))
    )
    (comp (ref "TP20")
      (value "Test Point")
      (footprint "TPS127")
      (fields (field (name "PART NUMBER") "SMD_PAD_1.27X1.27MM") (field (name "AUTHOR") "CERN DEM JLC"))
      (libsource (lib "Eletro-mechanical") (part "Test Point"))
    )
    (comp (ref "TP21")
      (value "Test Point")
      (footprint "TPS127")
      (fields (field (name "PART NUMBER") "SMD_PAD_1.27X1.27MM") (field (name "AUTHOR") "CERN DEM JLC"))
      (libsource (lib "Eletro-mechanical") (part "Test Point"))
    )
    (comp (ref "TP22")
      (value "Test Point")
      (footprint "TPS127")
      (fields (field (name "PART NUMBER") "SMD_PAD_1.27X1.27MM") (field (name "AUTHOR") "CERN DEM JLC"))
      (libsource (lib "Eletro-mechanical") (part "Test Point"))
    )
    (comp (ref "TP23")
      (value "Test Point")
      (footprint "TPS127")
      (fields (field (name "PART NUMBER") "SMD_PAD_1.27X1.27MM") (field (name "AUTHOR") "CERN DEM JLC"))
      (libsource (lib "Eletro-mechanical") (part "Test Point"))
    )
  )
  (nets
    (net (code "1") (name "/EN_ADC_AFE") (class "Default")
      (node (ref "IC18") (pin "3") (pinfunction "~{SHDN}_3") (pintype "input"))
      (node (ref "IC7") (pin "3") (pinfunction "~{SHDN}_3") (pintype "input"))
    )
    (net (code "2") (name "/FAN_PWM") (class "Default")
      (node (ref "C368") (pin "2") (pinfunction "2_2") (pintype "passive"))
    )
    (net (code "3") (name "/N12V0F") (class "Default")
      (node (ref "C248") (pin "2") (pinfunction "2_2") (pintype "passive"))
      (node (ref "C251") (pin "2") (pinfunction "2_2") (pintype "passive"))
      (node (ref "L3") (pin "2") (pinfunction "2_2") (pintype "passive"))
      (node (ref "L9") (pin "1") (pinfunction "1_1") (pintype "passive"))
    )
    (net (code "4") (name "/N12V0S") (class "Default")
      (node (ref "C247") (pin "2") (pinfunction "2_2") (pintype "passive"))
      (node (ref "IC23") (pin "5") (pinfunction "-Vout_5") (pintype "power_in"))
      (node (ref "L3") (pin "1") (pinfunction "1_1") (pintype "passive"))
    )
    (net (code "5") (name "/P12V0F") (class "Default")
      (node (ref "C183") (pin "2") (pinfunction "2_2") (pintype "passive"))
      (node (ref "C255") (pin "1") (pinfunction "1_1") (pintype "passive"))
      (node (ref "L44") (pin "2") (pinfunction "2_2") (pintype "passive"))
      (node (ref "L45") (pin "1") (pinfunction "1_1") (pintype "passive"))
    )
    (net (code "6") (name "/P12V0S") (class "Default")
      (node (ref "C250") (pin "1") (pinfunction "1_1") (pintype "passive"))
      (node (ref "IC23") (pin "3") (pinfunction "+Vout_3") (pintype "power_in"))
      (node (ref "L44") (pin "1") (pinfunction "1_1") (pintype "passive"))
    )
    (net (code "7") (name "/TACHO") (class "Default")
      (node (ref "R277") (pin "1") (pinfunction "1_1") (pintype "passive"))
    )
    (net (code "8") (name "GND") (class "Default")
      (node (ref "C179") (pin "1") (pinfunction "1_1") (pintype "passive"))
      (node (ref "C183") (pin "1") (pinfunction "1_1") (pintype "passive"))
      (node (ref "C245") (pin "1") (pinfunction "1_1") (pintype "passive"))
      (node (ref "C247") (pin "1") (pinfunction "1_1") (pintype "passive"))
      (node (ref "C248") (pin "1") (pinfunction "1_1") (pintype "passive"))
      (node (ref "C249") (pin "1") (pinfunction "1_1") (pintype "passive"))
      (node (ref "C250") (pin "2") (pinfunction "2_2") (pintype "passive"))
      (node (ref "C251") (pin "1") (pinfunction "1_1") (pintype "passive"))
      (node (ref "C252") (pin "1") (pinfunction "1_1") (pintype "passive"))
      (node (ref "C255") (pin "2") (pinfunction "2_2") (pintype "passive"))
      (node (ref "C268") (pin "1") (pinfunction "1_1") (pintype "passive"))
      (node (ref "C364") (pin "2") (pinfunction "2_2") (pintype "passive"))
      (node (ref "C365") (pin "1") (pinfunction "1_1") (pintype "passive"))
      (node (ref "C366") (pin "1") (pinfunction "1_1") (pintype "passive"))
      (node (ref "D3") (pin "1") (pinfunction "C_1") (pintype "passive"))
      (node (ref "D6") (pin "2") (pinfunction "A_2") (pintype "passive"))
      (node (ref "D8") (pin "1") (pinfunction "A_1") (pintype "passive"))
      (node (ref "IC18") (pin "1") (pinfunction "GND_1") (pintype "power_in"))
      (node (ref "IC23") (pin "1") (pinfunction "-Vin_1") (pintype "power_in"))
      (node (ref "IC23") (pin "4") (pinfunction "COM_4") (pintype "power_in"))
      (node (ref "IC7") (pin "2") (pinfunction "GND_2") (pintype "power_in"))
      (node (ref "J18") (pin "1") (pinfunction "1_1") (pintype "bidirectional"))
      (node (ref "LD11") (pin "1") (pinfunction "C_1") (pintype "passive"))
      (node (ref "LD14") (pin "1") (pinfunction "C_1") (pintype "passive"))
      (node (ref "LD15") (pin "1") (pinfunction "C_1") (pintype "passive"))
      (node (ref "LD16") (pin "1") (pinfunction "C_1") (pintype "passive"))
      (node (ref "LD17") (pin "1") (pinfunction "C_1") (pintype "passive"))
      (node (ref "LD18") (pin "1") (pinfunction "C_1") (pintype "passive"))
      (node (ref "LD19") (pin "1") (pinfunction "C_1") (pintype "passive"))
      (node (ref "LD20") (pin "1") (pinfunction "C_1") (pintype "passive"))
      (node (ref "LD21") (pin "2") (pinfunction "A_2") (pintype "passive"))
      (node (ref "LD4") (pin "1") (pinfunction "C_1") (pintype "passive"))
      (node (ref "R177") (pin "1") (pinfunction "1_1") (pintype "passive"))
      (node (ref "R203") (pin "1") (pinfunction "1_1") (pintype "passive"))
      (node (ref "R206") (pin "1") (pinfunction "1_1") (pintype "passive"))
      (node (ref "R209") (pin "1") (pinfunction "1_1") (pintype "passive"))
      (node (ref "R222") (pin "1") (pinfunction "1_1") (pintype "passive"))
      (node (ref "R23") (pin "1") (pinfunction "1_1") (pintype "passive"))
      (node (ref "R80") (pin "1") (pinfunction "1_1") (pintype "passive"))
      (node (ref "T11") (pin "4") (pinfunction "E_4") (pintype "passive"))
      (node (ref "T12") (pin "1") (pinfunction "E_1") (pintype "passive"))
      (node (ref "T12") (pin "4") (pinfunction "E_4") (pintype "passive"))
      (node (ref "T14") (pin "2") (pinfunction "S_2") (pintype "passive"))
      (node (ref "T3") (pin "1") (pinfunction "E_1") (pintype "passive"))
      (node (ref "T3") (pin "4") (pinfunction "E_4") (pintype "passive"))
      (node (ref "TP12") (pin "1") (pinfunction "1_1") (pintype "bidirectional"))
      (node (ref "TP17") (pin "1") (pinfunction "1_1") (pintype "bidirectional"))
      (node (ref "TP19") (pin "1") (pinfunction "1_1") (pintype "bidirectional"))
      (node (ref "TP20") (pin "1") (pinfunction "1_1") (pintype "bidirectional"))
      (node (ref "TP21") (pin "1") (pinfunction "1_1") (pintype "bidirectional"))
      (node (ref "TP22") (pin "1") (pinfunction "1_1") (pintype "bidirectional"))
      (node (ref "TP23") (pin "1") (pinfunction "1_1") (pintype "bidirectional"))
    )
    (net (code "9") (name "N11V5A") (class "Default")
      (node (ref "C366") (pin "2") (pinfunction "2_2") (pintype "passive"))
      (node (ref "D3") (pin "2") (pinfunction "A_2") (pintype "passive"))
      (node (ref "IC18") (pin "5") (pinfunction "OUT_5") (pintype "power_in"))
      (node (ref "R220") (pin "2") (pinfunction "2_2") (pintype "passive"))
      (node (ref "R53") (pin "2") (pinfunction "2_2") (pintype "passive"))
      (node (ref "TP11") (pin "1") (pinfunction "1_1") (pintype "bidirectional"))
    )
    (net (code "10") (name "N12V0A") (class "Default")
      (node (ref "C252") (pin "2") (pinfunction "2_2") (pintype "passive"))
      (node (ref "C365") (pin "2") (pinfunction "2_2") (pintype "passive"))
      (node (ref "IC18") (pin "2") (pinfunction "IN_2") (pintype "input"))
      (node (ref "L9") (pin "2") (pinfunction "2_2") (pintype "passive"))
    )
    (net (code "11") (name "Net-(D8A-COMAC)") (class "Default")
      (node (ref "D8") (pin "3") (pinfunction "COMAC_3") (pintype "passive"))
      (node (ref "J18") (pin "2") (pinfunction "2_2") (pintype "bidirectional"))
      (node (ref "T16") (pin "3") (pinfunction "D_3") (pintype "passive"))
    )
    (net (code "12") (name "Net-(D9A-A)") (class "Default")
      (node (ref "C368") (pin "1") (pinfunction "1_1") (pintype "passive"))
      (node (ref "D9") (pin "1") (pinfunction "A_1") (pintype "passive"))
      (node (ref "R262") (pin "1") (pinfunction "1_1") (pintype "passive"))
      (node (ref "T14") (pin "1") (pinfunction "G_1") (pintype "passive"))
    )
    (net (code "13") (name "Net-(IC7-ADJ)") (class "Default")
      (node (ref "IC7") (pin "4") (pinfunction "ADJ_4") (pintype "input"))
      (node (ref "R20") (pin "1") (pinfunction "1_1") (pintype "passive"))
      (node (ref "R23") (pin "2") (pinfunction "2_2") (pintype "passive"))
    )
    (net (code "14") (name "Net-(IC18-ADJ)") (class "Default")
      (node (ref "IC18") (pin "4") (pinfunction "ADJ_4") (pintype "input"))
      (node (ref "R53") (pin "1") (pinfunction "1_1") (pintype "passive"))
      (node (ref "R80") (pin "2") (pinfunction "2_2") (pintype "passive"))
    )
    (net (code "15") (name "Net-(J18-Pad3)") (class "Default")
      (node (ref "J18") (pin "3") (pinfunction "3_3") (pintype "bidirectional"))
      (node (ref "R276") (pin "2") (pinfunction "2_2") (pintype "passive"))
      (node (ref "R277") (pin "2") (pinfunction "2_2") (pintype "passive"))
    )
    (net (code "16") (name "Net-(LD1-C)") (class "Default")
      (node (ref "LD1") (pin "1") (pinfunction "C_1") (pintype "passive"))
      (node (ref "R202") (pin "1") (pinfunction "1_1") (pintype "passive"))
    )
    (net (code "17") (name "Net-(LD4-A)") (class "Default")
      (node (ref "LD4") (pin "2") (pinfunction "A_2") (pintype "passive"))
      (node (ref "R213") (pin "1") (pinfunction "1_1") (pintype "passive"))
    )
    (net (code "18") (name "Net-(LD9-C)") (class "Default")
      (node (ref "LD9") (pin "1") (pinfunction "C_1") (pintype "passive"))
      (node (ref "R204") (pin "1") (pinfunction "1_1") (pintype "passive"))
    )
    (net (code "19") (name "Net-(LD10-C)") (class "Default")
      (node (ref "LD10") (pin "1") (pinfunction "C_1") (pintype "passive"))
      (node (ref "R33") (pin "1") (pinfunction "1_1") (pintype "passive"))
    )
    (net (code "20") (name "Net-(LD11-A)") (class "Default")
      (node (ref "LD11") (pin "2") (pinfunction "A_2") (pintype "passive"))
      (node (ref "R218") (pin "1") (pinfunction "1_1") (pintype "passive"))
    )
    (net (code "21") (name "Net-(LD12-C)") (class "Default")
      (node (ref "LD12") (pin "1") (pinfunction "C_1") (pintype "passive"))
      (node (ref "R207") (pin "1") (pinfunction "1_1") (pintype "passive"))
    )
    (net (code "22") (name "Net-(LD13-C)") (class "Default")
      (node (ref "LD13") (pin "1") (pinfunction "C_1") (pintype "passive"))
      (node (ref "R221") (pin "1") (pinfunction "1_1") (pintype "passive"))
    )
    (net (code "23") (name "Net-(LD14-A)") (class "Default")
      (node (ref "LD14") (pin "2") (pinfunction "A_2") (pintype "passive"))
      (node (ref "R211") (pin "1") (pinfunction "1_1") (pintype "passive"))
    )
    (net (code "24") (name "Net-(LD15-A)") (class "Default")
      (node (ref "LD15") (pin "2") (pinfunction "A_2") (pintype "passive"))
      (node (ref "R212") (pin "1") (pinfunction "1_1") (pintype "passive"))
    )
    (net (code "25") (name "Net-(LD16-A)") (class "Default")
      (node (ref "LD16") (pin "2") (pinfunction "A_2") (pintype "passive"))
      (node (ref "R214") (pin "1") (pinfunction "1_1") (pintype "passive"))
    )
    (net (code "26") (name "Net-(LD17-A)") (class "Default")
      (node (ref "LD17") (pin "2") (pinfunction "A_2") (pintype "passive"))
      (node (ref "R215") (pin "1") (pinfunction "1_1") (pintype "passive"))
    )
    (net (code "27") (name "Net-(LD18-A)") (class "Default")
      (node (ref "LD18") (pin "2") (pinfunction "A_2") (pintype "passive"))
      (node (ref "R216") (pin "1") (pinfunction "1_1") (pintype "passive"))
    )
    (net (code "28") (name "Net-(LD19-A)") (class "Default")
      (node (ref "LD19") (pin "2") (pinfunction "A_2") (pintype "passive"))
      (node (ref "R217") (pin "1") (pinfunction "1_1") (pintype "passive"))
    )
    (net (code "29") (name "Net-(LD20-A)") (class "Default")
      (node (ref "LD20") (pin "2") (pinfunction "A_2") (pintype "passive"))
      (node (ref "R219") (pin "1") (pinfunction "1_1") (pintype "passive"))
    )
    (net (code "30") (name "Net-(LD21-C)") (class "Default")
      (node (ref "LD21") (pin "1") (pinfunction "C_1") (pintype "passive"))
      (node (ref "R220") (pin "1") (pinfunction "1_1") (pintype "passive"))
    )
    (net (code "31") (name "Net-(T3A-B)") (class "Default")
      (node (ref "R177") (pin "2") (pinfunction "2_2") (pintype "passive"))
      (node (ref "R182") (pin "1") (pinfunction "1_1") (pintype "passive"))
      (node (ref "T3") (pin "2") (pinfunction "B_2") (pintype "passive"))
    )
    (net (code "32") (name "Net-(T3A-C)") (class "Default")
      (node (ref "R33") (pin "2") (pinfunction "2_2") (pintype "passive"))
      (node (ref "T3") (pin "6") (pinfunction "C_6") (pintype "passive"))
    )
    (net (code "33") (name "Net-(T3B-B)") (class "Default")
      (node (ref "R183") (pin "1") (pinfunction "1_1") (pintype "passive"))
      (node (ref "R203") (pin "2") (pinfunction "2_2") (pintype "passive"))
      (node (ref "T3") (pin "5") (pinfunction "B_5") (pintype "passive"))
    )
    (net (code "34") (name "Net-(T3B-C)") (class "Default")
      (node (ref "R202") (pin "2") (pinfunction "2_2") (pintype "passive"))
      (node (ref "T3") (pin "3") (pinfunction "C_3") (pintype "passive"))
    )
    (net (code "35") (name "Net-(T11B-B)") (class "Default")
      (node (ref "R210") (pin "1") (pinfunction "1_1") (pintype "passive"))
      (node (ref "R222") (pin "2") (pinfunction "2_2") (pintype "passive"))
      (node (ref "T11") (pin "5") (pinfunction "B_5") (pintype "passive"))
    )
    (net (code "36") (name "Net-(T11B-C)") (class "Default")
      (node (ref "R221") (pin "2") (pinfunction "2_2") (pintype "passive"))
      (node (ref "T11") (pin "3") (pinfunction "C_3") (pintype "passive"))
    )
    (net (code "37") (name "Net-(T12A-B)") (class "Default")
      (node (ref "R205") (pin "1") (pinfunction "1_1") (pintype "passive"))
      (node (ref "R206") (pin "2") (pinfunction "2_2") (pintype "passive"))
      (node (ref "T12") (pin "2") (pinfunction "B_2") (pintype "passive"))
    )
    (net (code "38") (name "Net-(T12A-C)") (class "Default")
      (node (ref "R204") (pin "2") (pinfunction "2_2") (pintype "passive"))
      (node (ref "T12") (pin "6") (pinfunction "C_6") (pintype "passive"))
    )
    (net (code "39") (name "Net-(T12B-B)") (class "Default")
      (node (ref "R208") (pin "1") (pinfunction "1_1") (pintype "passive"))
      (node (ref "R209") (pin "2") (pinfunction "2_2") (pintype "passive"))
      (node (ref "T12") (pin "5") (pinfunction "B_5") (pintype "passive"))
    )
    (net (code "40") (name "Net-(T12B-C)") (class "Default")
      (node (ref "R207") (pin "2") (pinfunction "2_2") (pintype "passive"))
      (node (ref "T12") (pin "3") (pinfunction "C_3") (pintype "passive"))
    )
    (net (code "41") (name "Net-(T14-D)") (class "Default")
      (node (ref "R278") (pin "1") (pinfunction "1_1") (pintype "passive"))
      (node (ref "T14") (pin "3") (pinfunction "D_3") (pintype "passive"))
      (node (ref "T16") (pin "1") (pinfunction "G_1") (pintype "passive"))
    )
    (net (code "42") (name "P1V0") (class "Default")
      (node (ref "R182") (pin "2") (pinfunction "2_2") (pintype "passive"))
      (node (ref "TP13") (pin "1") (pinfunction "1_1") (pintype "bidirectional"))
    )
    (net (code "43") (name "P1V2") (class "Default")
      (node (ref "R183") (pin "2") (pinfunction "2_2") (pintype "passive"))
      (node (ref "TP14") (pin "1") (pinfunction "1_1") (pintype "bidirectional"))
    )
    (net (code "44") (name "P1V2A") (class "Default")
      (node (ref "R205") (pin "2") (pinfunction "2_2") (pintype "passive"))
      (node (ref "TP1") (pin "1") (pinfunction "1_1") (pintype "bidirectional"))
    )
    (net (code "45") (name "P1V5") (class "Default")
      (node (ref "R208") (pin "2") (pinfunction "2_2") (pintype "passive"))
      (node (ref "TP3") (pin "1") (pinfunction "1_1") (pintype "bidirectional"))
    )
    (net (code "46") (name "P1V8") (class "Default")
      (node (ref "R210") (pin "2") (pinfunction "2_2") (pintype "passive"))
      (node (ref "TP10") (pin "1") (pinfunction "1_1") (pintype "bidirectional"))
    )
    (net (code "47") (name "P2V5") (class "Default")
      (node (ref "R211") (pin "2") (pinfunction "2_2") (pintype "passive"))
      (node (ref "TP4") (pin "1") (pinfunction "1_1") (pintype "bidirectional"))
    )
    (net (code "48") (name "P3V3") (class "Default")
      (node (ref "D9") (pin "3") (pinfunction "COMAC_3") (pintype "passive"))
      (node (ref "R214") (pin "2") (pinfunction "2_2") (pintype "passive"))
      (node (ref "R262") (pin "2") (pinfunction "2_2") (pintype "passive"))
      (node (ref "R276") (pin "1") (pinfunction "1_1") (pintype "passive"))
      (node (ref "TP7") (pin "1") (pinfunction "1_1") (pintype "bidirectional"))
    )
    (net (code "49") (name "P3V3A") (class "Default")
      (node (ref "R213") (pin "2") (pinfunction "2_2") (pintype "passive"))
      (node (ref "TP6") (pin "1") (pinfunction "1_1") (pintype "bidirectional"))
    )
    (net (code "50") (name "P3V3_MP") (class "Default")
      (node (ref "R212") (pin "2") (pinfunction "2_2") (pintype "passive"))
      (node (ref "TP5") (pin "1") (pinfunction "1_1") (pintype "bidirectional"))
    )
    (net (code "51") (name "P3V6") (class "Default")
      (node (ref "R215") (pin "2") (pinfunction "2_2") (pintype "passive"))
      (node (ref "TP15") (pin "1") (pinfunction "1_1") (pintype "bidirectional"))
    )
    (net (code "52") (name "P5V0A") (class "Default")
      (node (ref "R216") (pin "2") (pinfunction "2_2") (pintype "passive"))
      (node (ref "TP16") (pin "1") (pinfunction "1_1") (pintype "bidirectional"))
    )
    (net (code "53") (name "P5V5") (class "Default")
      (node (ref "R217") (pin "2") (pinfunction "2_2") (pintype "passive"))
      (node (ref "TP8") (pin "1") (pinfunction "1_1") (pintype "bidirectional"))
    )
    (net (code "54") (name "P11V5A") (class "Default")
      (node (ref "C179") (pin "2") (pinfunction "2_2") (pintype "passive"))
      (node (ref "D6") (pin "1") (pinfunction "C_1") (pintype "passive"))
      (node (ref "IC7") (pin "5") (pinfunction "OUT_5") (pintype "power_in"))
      (node (ref "R20") (pin "2") (pinfunction "2_2") (pintype "passive"))
      (node (ref "R219") (pin "2") (pinfunction "2_2") (pintype "passive"))
      (node (ref "TP9") (pin "1") (pinfunction "1_1") (pintype "bidirectional"))
    )
    (net (code "55") (name "P12V0") (class "Default")
      (node (ref "C249") (pin "2") (pinfunction "2_2") (pintype "passive"))
      (node (ref "C268") (pin "2") (pinfunction "2_2") (pintype "passive"))
      (node (ref "IC23") (pin "2") (pinfunction "+Vin_2") (pintype "power_in"))
      (node (ref "LD1") (pin "2") (pinfunction "A_2") (pintype "passive"))
      (node (ref "LD10") (pin "2") (pinfunction "A_2") (pintype "passive"))
      (node (ref "LD12") (pin "2") (pinfunction "A_2") (pintype "passive"))
      (node (ref "LD13") (pin "2") (pinfunction "A_2") (pintype "passive"))
      (node (ref "LD9") (pin "2") (pinfunction "A_2") (pintype "passive"))
      (node (ref "R218") (pin "2") (pinfunction "2_2") (pintype "passive"))
      (node (ref "R278") (pin "2") (pinfunction "2_2") (pintype "passive"))
      (node (ref "T16") (pin "2") (pinfunction "S_2") (pintype "passive"))
      (node (ref "TP18") (pin "1") (pinfunction "1_1") (pintype "bidirectional"))
    )
    (net (code "56") (name "P12V0A") (class "Default")
      (node (ref "C245") (pin "2") (pinfunction "2_2") (pintype "passive"))
      (node (ref "C364") (pin "1") (pinfunction "1_1") (pintype "passive"))
      (node (ref "IC7") (pin "1") (pinfunction "IN_1") (pintype "input"))
      (node (ref "L45") (pin "2") (pinfunction "2_2") (pintype "passive"))
    )
    (net (code "57") (name "unconnected-(D8B-C-Pad2)") (class "Default")
      (node (ref "D8") (pin "2") (pinfunction "C_2") (pintype "passive+no_connect"))
    )
    (net (code "58") (name "unconnected-(D9B-C-Pad2)") (class "Default")
      (node (ref "D9") (pin "2") (pinfunction "C_2") (pintype "passive+no_connect"))
    )
    (net (code "59") (name "unconnected-(T11A-B-Pad2)") (class "Default")
      (node (ref "T11") (pin "2") (pinfunction "B_2") (pintype "passive+no_connect"))
    )
    (net (code "60") (name "unconnected-(T11A-C-Pad6)") (class "Default")
      (node (ref "T11") (pin "6") (pinfunction "C_6") (pintype "passive+no_connect"))
    )
    (net (code "61") (name "unconnected-(T11A-E-Pad1)") (class "Default")
      (node (ref "T11") (pin "1") (pinfunction "E_1") (pintype "passive+no_connect"))
    )
  )
)
